# MCU_64.net
KiCad netlist of a schematic drawn in Altium Designer
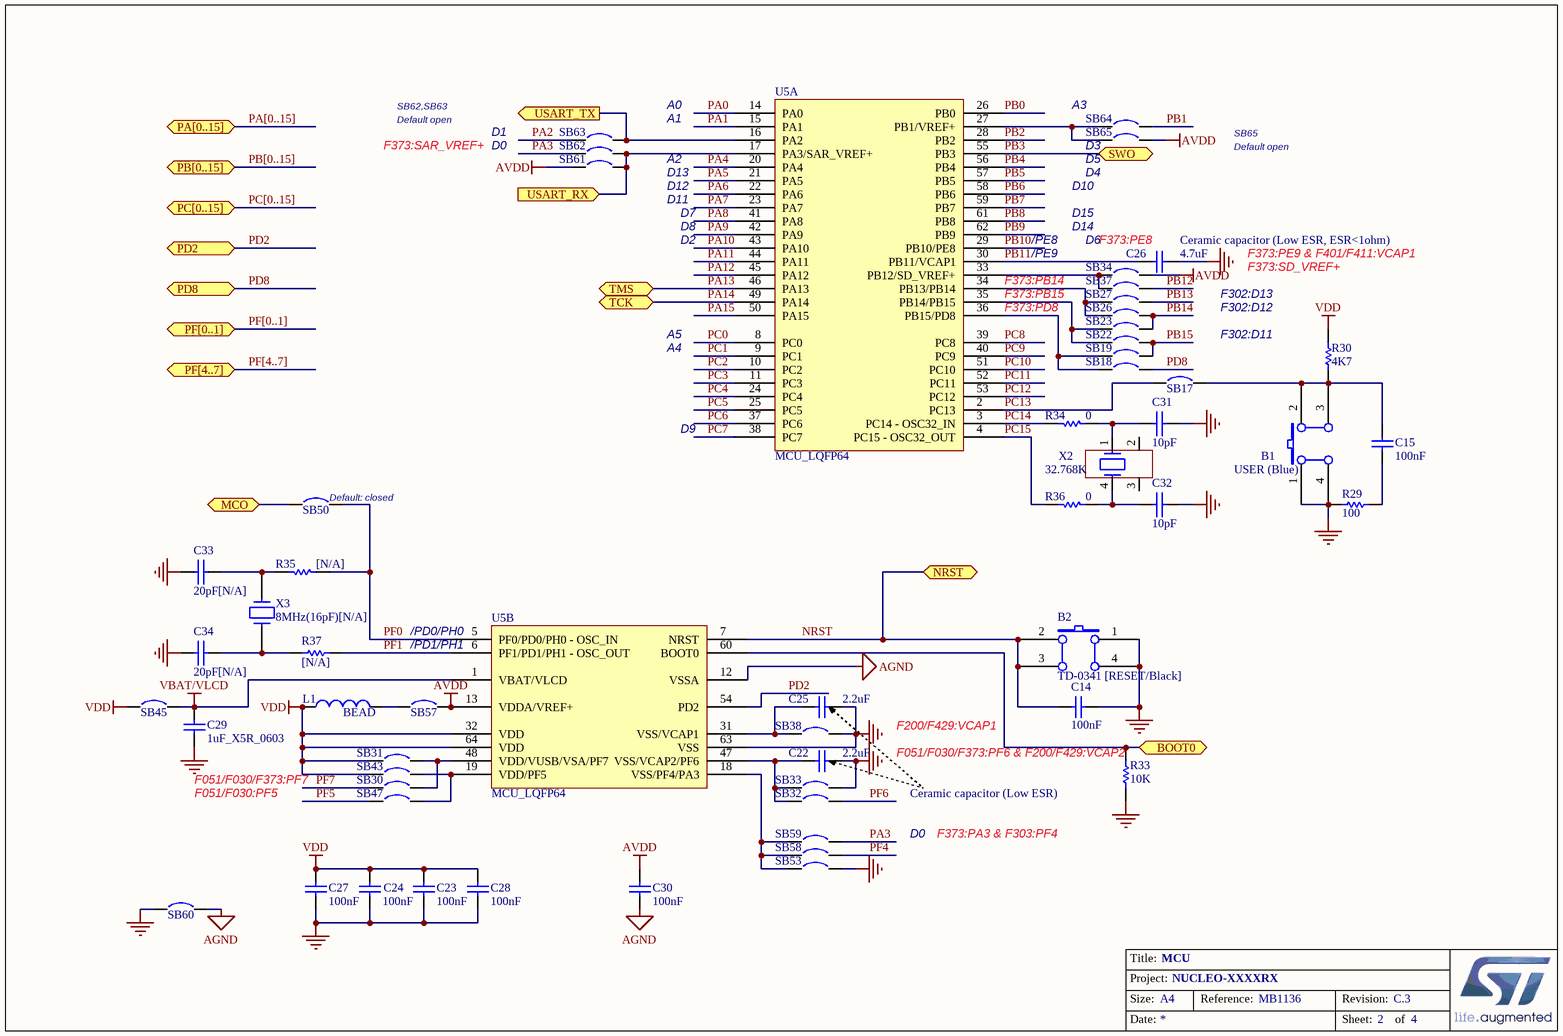
[diagram p0: MCU_64.SchDoc]

(export (version "E")
  (design (tool "Eeschema 10.0.6"))
  (components
    (comp (ref "B1")
      (value "USER (Blue)")
      (footprint "PB10")
      (description "SE PUSHBUTTON")
      (libsource (lib "Documents") (part "SW PUSHBUTTON"))
    )
    (comp (ref "B2")
      (value "TD-0341 [RESET/Black]")
      (footprint "PB10")
      (description "SE PUSHBUTTON")
      (libsource (lib "Documents") (part "SW PUSHBUTTON"))
    )
    (comp (ref "C14")
      (value "100nF")
      (footprint "0603C")
      (description "Capacitor")
      (fields (field (name "PUBLISHER") "Altium Limited"))
      (libsource (lib "Miscellaneous Devices") (part "CAP"))
    )
    (comp (ref "C15")
      (value "100nF")
      (footprint "0603C")
      (description "Capacitor")
      (fields (field (name "PUBLISHER") "Altium Limited"))
      (libsource (lib "Miscellaneous Devices") (part "CAP"))
    )
    (comp (ref "C22")
      (value "2.2uF")
      (footprint "TAN-A")
      (description "Capacitor,2.2uF,16V, X7R,10%,0805,YAGEO")
      (libsource (lib "MCD_TOOLS") (part "Cap_2.2uF_X7R_10%_0805"))
    )
    (comp (ref "C23")
      (value "100nF")
      (footprint "0603C")
      (description "Capacitor")
      (fields (field (name "PUBLISHER") "Altium Limited"))
      (libsource (lib "Miscellaneous Devices") (part "Cap"))
    )
    (comp (ref "C24")
      (value "100nF")
      (footprint "0603C")
      (description "Capacitor")
      (fields (field (name "PUBLISHER") "Altium Limited"))
      (libsource (lib "Miscellaneous Devices") (part "Cap"))
    )
    (comp (ref "C25")
      (value "2.2uF")
      (footprint "TAN-A")
      (description "Capacitor,2.2uF,16V, X7R,10%,0805,YAGEO")
      (libsource (lib "MCD_TOOLS") (part "Cap_2.2uF_X7R_10%_0805"))
    )
    (comp (ref "C26")
      (value "4.7uF")
      (footprint "TAN-A")
      (description "Capacitor,2.2uF,16V, X7R,10%,0805,YAGEO")
      (libsource (lib "MCD_TOOLS") (part "Cap_2.2uF_X7R_10%_0805"))
    )
    (comp (ref "C27")
      (value "100nF")
      (footprint "0603C")
      (description "Capacitor")
      (fields (field (name "PUBLISHER") "Altium Limited"))
      (libsource (lib "Miscellaneous Devices") (part "Cap"))
    )
    (comp (ref "C28")
      (value "100nF")
      (footprint "0603C")
      (description "Capacitor")
      (fields (field (name "PUBLISHER") "Altium Limited"))
      (libsource (lib "Miscellaneous Devices") (part "Cap"))
    )
    (comp (ref "C29")
      (value "1uF_X5R_0603")
      (footprint "0603C")
      (description "0603  X5R 1µF")
      (fields (field (name "TOLERANCE") "10%"))
      (libsource (lib "MB963_1") (part "CAP SMD 0603  X5R 1µF 25V 10%"))
    )
    (comp (ref "C30")
      (value "100nF")
      (footprint "0603C")
      (description "Capacitor")
      (fields (field (name "PUBLISHER") "Altium Limited"))
      (libsource (lib "Miscellaneous Devices") (part "Cap"))
    )
    (comp (ref "C31")
      (value "10pF")
      (footprint "0603C")
      (description "Capacitor")
      (libsource (lib "") (part "CAP_1"))
    )
    (comp (ref "C32")
      (value "10pF")
      (footprint "0603C")
      (description "Capacitor")
      (libsource (lib "") (part "CAP_1"))
    )
    (comp (ref "C33")
      (value "20pF[N/A]")
      (footprint "0603C")
      (description "Capacitor")
      (libsource (lib "*") (part "CAP"))
    )
    (comp (ref "C34")
      (value "20pF[N/A]")
      (footprint "0603C")
      (description "Capacitor")
      (libsource (lib "*") (part "CAP"))
    )
    (comp (ref "L1")
      (value "BEAD")
      (footprint "0603L")
      (description "Inductor")
      (fields (field (name "PUBLISHER") "Altium Limited"))
      (libsource (lib "Miscellaneous Devices") (part "Inductor"))
    )
    (comp (ref "R29")
      (value "100")
      (footprint "0603R")
      (description "Resistor")
      (fields (field (name "PUBLISHER") "Altium Limited"))
      (libsource (lib "") (part "Res1_1"))
    )
    (comp (ref "R30")
      (value "4K7")
      (footprint "0603R")
      (description "Resistor")
      (fields (field (name "PUBLISHER") "Altium Limited"))
      (libsource (lib "Miscellaneous Devices") (part "res1"))
    )
    (comp (ref "R33")
      (value "10K")
      (footprint "0603R")
      (description "Resistor")
      (fields (field (name "PUBLISHER") "Altium Limited"))
      (libsource (lib "Miscellaneous Devices") (part "res1"))
    )
    (comp (ref "R34")
      (value "0")
      (footprint "0603R")
      (description "Resistor")
      (fields (field (name "PUBLISHER") "Altium Limited"))
      (libsource (lib "Miscellaneous Devices") (part "Res1"))
    )
    (comp (ref "R35")
      (value "[N/A]")
      (footprint "0603R")
      (description "Resistor")
      (fields (field (name "PUBLISHER") "Altium Limited"))
      (libsource (lib "Miscellaneous Devices") (part "Res1"))
    )
    (comp (ref "R36")
      (value "0")
      (footprint "0603R")
      (description "Resistor")
      (fields (field (name "PUBLISHER") "Altium Limited"))
      (libsource (lib "Miscellaneous Devices") (part "Res1"))
    )
    (comp (ref "R37")
      (value "[N/A]")
      (footprint "0603R")
      (description "Resistor")
      (fields (field (name "PUBLISHER") "Altium Limited"))
      (libsource (lib "") (part "Res1_1"))
    )
    (comp (ref "SB17")
      (value "Circuit Breaker")
      (footprint "JP2_SMD")
      (fields (field (name "PUBLISHER") "Altium Limited"))
      (libsource (lib "MCD_TOOLS") (part "Circuit Breaker"))
    )
    (comp (ref "SB18")
      (value "Circuit Breaker")
      (footprint "JP2_SMD")
      (fields (field (name "PUBLISHER") "Altium Limited"))
      (libsource (lib "MCD_TOOLS") (part "Circuit Breaker"))
    )
    (comp (ref "SB19")
      (value "Circuit Breaker")
      (footprint "JP2_SMD")
      (fields (field (name "PUBLISHER") "Altium Limited"))
      (libsource (lib "MCD_TOOLS") (part "Circuit Breaker"))
    )
    (comp (ref "SB22")
      (value "Circuit Breaker")
      (footprint "JP2_SMD")
      (fields (field (name "PUBLISHER") "Altium Limited"))
      (libsource (lib "MCD_TOOLS") (part "Circuit Breaker"))
    )
    (comp (ref "SB23")
      (value "Circuit Breaker")
      (footprint "JP2_SMD")
      (fields (field (name "PUBLISHER") "Altium Limited"))
      (libsource (lib "MCD_TOOLS") (part "Circuit Breaker"))
    )
    (comp (ref "SB26")
      (value "Circuit Breaker")
      (footprint "JP2_SMD")
      (fields (field (name "PUBLISHER") "Altium Limited"))
      (libsource (lib "MCD_TOOLS") (part "Circuit Breaker"))
    )
    (comp (ref "SB27")
      (value "Circuit Breaker")
      (footprint "JP2_SMD")
      (fields (field (name "PUBLISHER") "Altium Limited"))
      (libsource (lib "MCD_TOOLS") (part "Circuit Breaker"))
    )
    (comp (ref "SB30")
      (value "Circuit Breaker")
      (footprint "JP2_SMD")
      (fields (field (name "PUBLISHER") "Altium Limited"))
      (libsource (lib "MCD_TOOLS") (part "Circuit Breaker"))
    )
    (comp (ref "SB31")
      (value "Circuit Breaker")
      (footprint "JP2_SMD")
      (fields (field (name "PUBLISHER") "Altium Limited"))
      (libsource (lib "MCD_TOOLS") (part "Circuit Breaker"))
    )
    (comp (ref "SB32")
      (value "Circuit Breaker")
      (footprint "JP2_SMD")
      (fields (field (name "PUBLISHER") "Altium Limited"))
      (libsource (lib "MCD_TOOLS") (part "Circuit Breaker"))
    )
    (comp (ref "SB33")
      (value "Circuit Breaker")
      (footprint "JP2_SMD")
      (fields (field (name "PUBLISHER") "Altium Limited"))
      (libsource (lib "MCD_TOOLS") (part "Circuit Breaker"))
    )
    (comp (ref "SB34")
      (value "Circuit Breaker")
      (footprint "JP2_SMD")
      (fields (field (name "PUBLISHER") "Altium Limited"))
      (libsource (lib "MCD_TOOLS") (part "Circuit Breaker"))
    )
    (comp (ref "SB37")
      (value "Circuit Breaker")
      (footprint "JP2_SMD")
      (fields (field (name "PUBLISHER") "Altium Limited"))
      (libsource (lib "MCD_TOOLS") (part "Circuit Breaker"))
    )
    (comp (ref "SB38")
      (value "Circuit Breaker")
      (footprint "JP2_SMD")
      (fields (field (name "PUBLISHER") "Altium Limited"))
      (libsource (lib "MCD_TOOLS") (part "Circuit Breaker"))
    )
    (comp (ref "SB43")
      (value "Circuit Breaker")
      (footprint "JP2_SMD")
      (fields (field (name "PUBLISHER") "Altium Limited"))
      (libsource (lib "MCD_TOOLS") (part "Circuit Breaker"))
    )
    (comp (ref "SB45")
      (value "Circuit Breaker")
      (footprint "JP2_SMD")
      (fields (field (name "PUBLISHER") "Altium Limited"))
      (libsource (lib "MCD_TOOLS") (part "Circuit Breaker"))
    )
    (comp (ref "SB47")
      (value "Circuit Breaker")
      (footprint "JP2_SMD")
      (fields (field (name "PUBLISHER") "Altium Limited"))
      (libsource (lib "MCD_TOOLS") (part "Circuit Breaker"))
    )
    (comp (ref "SB50")
      (value "Circuit Breaker")
      (footprint "JP2_SMD")
      (fields (field (name "PUBLISHER") "Altium Limited"))
      (libsource (lib "MCD_TOOLS") (part "Circuit Breaker"))
    )
    (comp (ref "SB53")
      (value "Circuit Breaker")
      (footprint "JP2_SMD")
      (fields (field (name "PUBLISHER") "Altium Limited"))
      (libsource (lib "MCD_TOOLS") (part "Circuit Breaker"))
    )
    (comp (ref "SB57")
      (value "Circuit Breaker")
      (footprint "JP2_SMD")
      (fields (field (name "PUBLISHER") "Altium Limited"))
      (libsource (lib "MCD_TOOLS") (part "Circuit Breaker"))
    )
    (comp (ref "SB58")
      (value "Circuit Breaker")
      (footprint "JP2_SMD")
      (fields (field (name "PUBLISHER") "Altium Limited"))
      (libsource (lib "MCD_TOOLS") (part "Circuit Breaker"))
    )
    (comp (ref "SB59")
      (value "Circuit Breaker")
      (footprint "JP2_SMD")
      (fields (field (name "PUBLISHER") "Altium Limited"))
      (libsource (lib "MCD_TOOLS") (part "Circuit Breaker"))
    )
    (comp (ref "SB60")
      (value "Circuit Breaker")
      (footprint "JP2_SMD")
      (fields (field (name "PUBLISHER") "Altium Limited"))
      (libsource (lib "MCD_TOOLS") (part "Circuit Breaker"))
    )
    (comp (ref "SB61")
      (value "Circuit Breaker")
      (footprint "JP2_SMD")
      (fields (field (name "PUBLISHER") "Altium Limited"))
      (libsource (lib "MCD_TOOLS") (part "Circuit Breaker"))
    )
    (comp (ref "SB62")
      (value "Circuit Breaker")
      (footprint "JP2_SMD")
      (fields (field (name "PUBLISHER") "Altium Limited"))
      (libsource (lib "MCD_TOOLS") (part "Circuit Breaker"))
    )
    (comp (ref "SB63")
      (value "Circuit Breaker")
      (footprint "JP2_SMD")
      (fields (field (name "PUBLISHER") "Altium Limited"))
      (libsource (lib "MCD_TOOLS") (part "Circuit Breaker"))
    )
    (comp (ref "SB64")
      (value "Circuit Breaker")
      (footprint "JP2_SMD")
      (fields (field (name "PUBLISHER") "Altium Limited"))
      (libsource (lib "MCD_TOOLS") (part "Circuit Breaker"))
    )
    (comp (ref "SB65")
      (value "Circuit Breaker")
      (footprint "JP2_SMD")
      (fields (field (name "PUBLISHER") "Altium Limited"))
      (libsource (lib "MCD_TOOLS") (part "Circuit Breaker"))
    )
    (comp (ref "U5")
      (value "MCU_LQFP64")
      (footprint "LQFP64")
      (libsource (lib "Nucleo_64") (part "MCU_LQFP64"))
    )
    (comp (ref "X2") (value "32.768K") (footprint "XTAL_4SM_8X3R8") (libsource (lib "*") (part "MC306")))
    (comp (ref "X3")
      (value "8MHz(16pF)[N/A]")
      (footprint "XTAL1")
      (description "Crystal")
      (libsource (lib "*") (part "CRYSTAL"))
    )
  )
  (nets
    (net (code "1") (name "/BOOT0") (class "Default")
      (node (ref "R33") (pin "1") (pinfunction "1_1") (pintype "passive"))
      (node (ref "U5") (pin "60") (pinfunction "BOOT0_60") (pintype "passive"))
    )
    (net (code "2") (name "/MCO") (class "Default")
      (node (ref "SB50") (pin "1") (pinfunction "1_1") (pintype "passive"))
    )
    (net (code "3") (name "/NRST") (class "Default")
      (node (ref "B2") (pin "2") (pinfunction "B0_2") (pintype "passive"))
      (node (ref "B2") (pin "3") (pinfunction "B1_3") (pintype "passive"))
      (node (ref "C14") (pin "2") (pinfunction "2_2") (pintype "passive"))
      (node (ref "U5") (pin "7") (pinfunction "NRST_7") (pintype "passive"))
    )
    (net (code "4") (name "/PA0") (class "Default")
      (node (ref "U5") (pin "14") (pinfunction "PA0_14") (pintype "passive"))
    )
    (net (code "5") (name "/PA1") (class "Default")
      (node (ref "U5") (pin "15") (pinfunction "PA1_15") (pintype "passive"))
    )
    (net (code "6") (name "/PA2") (class "Default")
      (node (ref "SB63") (pin "1") (pinfunction "1_1") (pintype "passive"))
    )
    (net (code "7") (name "/PA3") (class "Default")
      (node (ref "SB59") (pin "2") (pinfunction "2_2") (pintype "passive"))
      (node (ref "SB62") (pin "1") (pinfunction "1_1") (pintype "passive"))
    )
    (net (code "8") (name "/PA4") (class "Default")
      (node (ref "U5") (pin "20") (pinfunction "PA4_20") (pintype "passive"))
    )
    (net (code "9") (name "/PA5") (class "Default")
      (node (ref "U5") (pin "21") (pinfunction "PA5_21") (pintype "passive"))
    )
    (net (code "10") (name "/PA6") (class "Default")
      (node (ref "U5") (pin "22") (pinfunction "PA6_22") (pintype "passive"))
    )
    (net (code "11") (name "/PA7") (class "Default")
      (node (ref "U5") (pin "23") (pinfunction "PA7_23") (pintype "passive"))
    )
    (net (code "12") (name "/PA8") (class "Default")
      (node (ref "U5") (pin "41") (pinfunction "PA8_41") (pintype "passive"))
    )
    (net (code "13") (name "/PA9") (class "Default")
      (node (ref "U5") (pin "42") (pinfunction "PA9_42") (pintype "passive"))
    )
    (net (code "14") (name "/PA10") (class "Default")
      (node (ref "U5") (pin "43") (pinfunction "PA10_43") (pintype "passive"))
    )
    (net (code "15") (name "/PA11") (class "Default")
      (node (ref "U5") (pin "44") (pinfunction "PA11_44") (pintype "passive"))
    )
    (net (code "16") (name "/PA12") (class "Default")
      (node (ref "U5") (pin "45") (pinfunction "PA12_45") (pintype "passive"))
    )
    (net (code "17") (name "/PA13") (class "Default")
      (node (ref "U5") (pin "46") (pinfunction "PA13_46") (pintype "passive"))
    )
    (net (code "18") (name "/PA14") (class "Default")
      (node (ref "U5") (pin "49") (pinfunction "PA14_49") (pintype "passive"))
    )
    (net (code "19") (name "/PA15") (class "Default")
      (node (ref "U5") (pin "50") (pinfunction "PA15_50") (pintype "passive"))
    )
    (net (code "21") (name "/PB0") (class "Default")
      (node (ref "U5") (pin "26") (pinfunction "PB0_26") (pintype "passive"))
    )
    (net (code "22") (name "/PB1") (class "Default")
      (node (ref "SB64") (pin "2") (pinfunction "2_2") (pintype "passive"))
    )
    (net (code "23") (name "/PB2") (class "Default")
      (node (ref "U5") (pin "28") (pinfunction "PB2_28") (pintype "passive"))
    )
    (net (code "24") (name "/PB3") (class "Default")
      (node (ref "U5") (pin "55") (pinfunction "PB3_55") (pintype "passive"))
    )
    (net (code "25") (name "/PB4") (class "Default")
      (node (ref "U5") (pin "56") (pinfunction "PB4_56") (pintype "passive"))
    )
    (net (code "26") (name "/PB5") (class "Default")
      (node (ref "U5") (pin "57") (pinfunction "PB5_57") (pintype "passive"))
    )
    (net (code "27") (name "/PB6") (class "Default")
      (node (ref "U5") (pin "58") (pinfunction "PB6_58") (pintype "passive"))
    )
    (net (code "28") (name "/PB7") (class "Default")
      (node (ref "U5") (pin "59") (pinfunction "PB7_59") (pintype "passive"))
    )
    (net (code "29") (name "/PB8") (class "Default")
      (node (ref "U5") (pin "61") (pinfunction "PB8_61") (pintype "passive"))
    )
    (net (code "30") (name "/PB9") (class "Default")
      (node (ref "U5") (pin "62") (pinfunction "PB9_62") (pintype "passive"))
    )
    (net (code "31") (name "/PB10") (class "Default")
      (node (ref "U5") (pin "29") (pinfunction "PB10/PE8_29") (pintype "passive"))
    )
    (net (code "32") (name "/PB11") (class "Default")
      (node (ref "C26") (pin "1") (pinfunction "1_1") (pintype "passive"))
      (node (ref "U5") (pin "30") (pinfunction "PB11/VCAP1_30") (pintype "passive"))
    )
    (net (code "33") (name "/PB12") (class "Default")
      (node (ref "SB37") (pin "2") (pinfunction "2_2") (pintype "passive"))
    )
    (net (code "34") (name "/PB13") (class "Default")
      (node (ref "SB27") (pin "2") (pinfunction "2_2") (pintype "passive"))
    )
    (net (code "35") (name "/PB14") (class "Default")
      (node (ref "SB23") (pin "2") (pinfunction "2_2") (pintype "passive"))
      (node (ref "SB26") (pin "2") (pinfunction "2_2") (pintype "passive"))
    )
    (net (code "36") (name "/PB15") (class "Default")
      (node (ref "SB19") (pin "2") (pinfunction "2_2") (pintype "passive"))
      (node (ref "SB22") (pin "2") (pinfunction "2_2") (pintype "passive"))
    )
    (net (code "38") (name "/PC0") (class "Default")
      (node (ref "U5") (pin "8") (pinfunction "PC0_8") (pintype "passive"))
    )
    (net (code "39") (name "/PC1") (class "Default")
      (node (ref "U5") (pin "9") (pinfunction "PC1_9") (pintype "passive"))
    )
    (net (code "40") (name "/PC2") (class "Default")
      (node (ref "U5") (pin "10") (pinfunction "PC2_10") (pintype "passive"))
    )
    (net (code "41") (name "/PC3") (class "Default")
      (node (ref "U5") (pin "11") (pinfunction "PC3_11") (pintype "passive"))
    )
    (net (code "42") (name "/PC4") (class "Default")
      (node (ref "U5") (pin "24") (pinfunction "PC4_24") (pintype "passive"))
    )
    (net (code "43") (name "/PC5") (class "Default")
      (node (ref "U5") (pin "25") (pinfunction "PC5_25") (pintype "passive"))
    )
    (net (code "44") (name "/PC6") (class "Default")
      (node (ref "U5") (pin "37") (pinfunction "PC6_37") (pintype "passive"))
    )
    (net (code "45") (name "/PC7") (class "Default")
      (node (ref "U5") (pin "38") (pinfunction "PC7_38") (pintype "passive"))
    )
    (net (code "46") (name "/PC8") (class "Default")
      (node (ref "U5") (pin "39") (pinfunction "PC8_39") (pintype "passive"))
    )
    (net (code "47") (name "/PC9") (class "Default")
      (node (ref "U5") (pin "40") (pinfunction "PC9_40") (pintype "passive"))
    )
    (net (code "48") (name "/PC10") (class "Default")
      (node (ref "U5") (pin "51") (pinfunction "PC10_51") (pintype "passive"))
    )
    (net (code "49") (name "/PC11") (class "Default")
      (node (ref "U5") (pin "52") (pinfunction "PC11_52") (pintype "passive"))
    )
    (net (code "50") (name "/PC12") (class "Default")
      (node (ref "U5") (pin "53") (pinfunction "PC12_53") (pintype "passive"))
    )
    (net (code "51") (name "/PC13") (class "Default")
      (node (ref "SB17") (pin "1") (pinfunction "1_1") (pintype "passive"))
      (node (ref "U5") (pin "2") (pinfunction "PC13_2") (pintype "passive"))
    )
    (net (code "52") (name "/PC14") (class "Default")
      (node (ref "R34") (pin "2") (pinfunction "2_2") (pintype "passive"))
      (node (ref "U5") (pin "3") (pinfunction "PC14_-_OSC32_IN_3") (pintype "passive"))
    )
    (net (code "53") (name "/PC15") (class "Default")
      (node (ref "R36") (pin "2") (pinfunction "2_2") (pintype "passive"))
      (node (ref "U5") (pin "4") (pinfunction "PC15_-_OSC32_OUT_4") (pintype "passive"))
    )
    (net (code "55") (name "/PD2") (class "Default")
      (node (ref "U5") (pin "54") (pinfunction "PD2_54") (pintype "passive"))
    )
    (net (code "56") (name "/PD8") (class "Default")
      (node (ref "SB18") (pin "2") (pinfunction "2_2") (pintype "passive"))
    )
    (net (code "57") (name "/PF0") (class "Default")
      (node (ref "R35") (pin "1") (pinfunction "1_1") (pintype "passive"))
      (node (ref "SB50") (pin "2") (pinfunction "2_2") (pintype "passive"))
      (node (ref "U5") (pin "5") (pinfunction "PF0/PD0/PH0_-_OSC_IN_5") (pintype "passive"))
    )
    (net (code "58") (name "/PF1") (class "Default")
      (node (ref "R37") (pin "1") (pinfunction "1_1") (pintype "passive"))
      (node (ref "U5") (pin "6") (pinfunction "PF1/PD1/PH1_-_OSC_OUT_6") (pintype "passive"))
    )
    (net (code "59") (name "/PF4") (class "Default")
      (node (ref "SB58") (pin "2") (pinfunction "2_2") (pintype "passive"))
    )
    (net (code "60") (name "/PF5") (class "Default")
      (node (ref "SB47") (pin "1") (pinfunction "1_1") (pintype "passive"))
    )
    (net (code "61") (name "/PF6") (class "Default")
      (node (ref "SB32") (pin "2") (pinfunction "2_2") (pintype "passive"))
    )
    (net (code "62") (name "/PF7") (class "Default")
      (node (ref "SB30") (pin "1") (pinfunction "1_1") (pintype "passive"))
    )
    (net (code "65") (name "/USART_RX") (class "Default")
      (node (ref "SB61") (pin "2") (pinfunction "2_2") (pintype "passive"))
      (node (ref "SB62") (pin "2") (pinfunction "2_2") (pintype "passive"))
      (node (ref "U5") (pin "17") (pinfunction "PA3/SAR_VREF+_17") (pintype "passive"))
    )
    (net (code "66") (name "/USART_TX") (class "Default")
      (node (ref "SB63") (pin "2") (pinfunction "2_2") (pintype "passive"))
      (node (ref "U5") (pin "16") (pinfunction "PA2_16") (pintype "passive"))
    )
    (net (code "67") (name "AGND") (class "Default")
      (node (ref "C30") (pin "2") (pinfunction "2_2") (pintype "passive"))
      (node (ref "SB60") (pin "2") (pinfunction "2_2") (pintype "passive"))
      (node (ref "U5") (pin "12") (pinfunction "VSSA_12") (pintype "passive"))
    )
    (net (code "68") (name "AVDD") (class "Default")
      (node (ref "C30") (pin "1") (pinfunction "1_1") (pintype "passive"))
      (node (ref "SB34") (pin "2") (pinfunction "2_2") (pintype "passive"))
      (node (ref "SB57") (pin "2") (pinfunction "2_2") (pintype "passive"))
      (node (ref "SB61") (pin "1") (pinfunction "1_1") (pintype "passive"))
      (node (ref "SB65") (pin "2") (pinfunction "2_2") (pintype "passive"))
      (node (ref "U5") (pin "13") (pinfunction "VDDA/VREF+_13") (pintype "passive"))
    )
    (net (code "69") (name "GND") (class "Default")
      (node (ref "B1") (pin "1") (pinfunction "A0_1") (pintype "passive"))
      (node (ref "B1") (pin "4") (pinfunction "A1_4") (pintype "passive"))
      (node (ref "B2") (pin "1") (pinfunction "A0_1") (pintype "passive"))
      (node (ref "B2") (pin "4") (pinfunction "A1_4") (pintype "passive"))
      (node (ref "C14") (pin "1") (pinfunction "1_1") (pintype "passive"))
      (node (ref "C22") (pin "2") (pinfunction "2_2") (pintype "passive"))
      (node (ref "C23") (pin "2") (pinfunction "2_2") (pintype "passive"))
      (node (ref "C24") (pin "2") (pinfunction "2_2") (pintype "passive"))
      (node (ref "C25") (pin "2") (pinfunction "2_2") (pintype "passive"))
      (node (ref "C26") (pin "2") (pinfunction "2_2") (pintype "passive"))
      (node (ref "C27") (pin "2") (pinfunction "2_2") (pintype "passive"))
      (node (ref "C28") (pin "2") (pinfunction "2_2") (pintype "passive"))
      (node (ref "C29") (pin "2") (pinfunction "2_2") (pintype "passive"))
      (node (ref "C31") (pin "2") (pinfunction "2_2") (pintype "passive"))
      (node (ref "C32") (pin "2") (pinfunction "2_2") (pintype "passive"))
      (node (ref "C33") (pin "2") (pinfunction "2_2") (pintype "passive"))
      (node (ref "C34") (pin "2") (pinfunction "2_2") (pintype "passive"))
      (node (ref "R29") (pin "1") (pinfunction "1_1") (pintype "passive"))
      (node (ref "R33") (pin "2") (pinfunction "2_2") (pintype "passive"))
      (node (ref "SB33") (pin "2") (pinfunction "2_2") (pintype "passive"))
      (node (ref "SB38") (pin "2") (pinfunction "2_2") (pintype "passive"))
      (node (ref "SB53") (pin "2") (pinfunction "2_2") (pintype "passive"))
      (node (ref "SB60") (pin "1") (pinfunction "1_1") (pintype "passive"))
      (node (ref "U5") (pin "63") (pinfunction "VSS_63") (pintype "passive"))
    )
    (net (code "70") (name "Net-(B1-B0)") (class "Default")
      (node (ref "B1") (pin "2") (pinfunction "B0_2") (pintype "passive"))
      (node (ref "B1") (pin "3") (pinfunction "B1_3") (pintype "passive"))
      (node (ref "C15") (pin "2") (pinfunction "2_2") (pintype "passive"))
      (node (ref "R30") (pin "1") (pinfunction "1_1") (pintype "passive"))
      (node (ref "SB17") (pin "2") (pinfunction "2_2") (pintype "passive"))
    )
    (net (code "71") (name "Net-(C15-Pad1)") (class "Default")
      (node (ref "C15") (pin "1") (pinfunction "1_1") (pintype "passive"))
      (node (ref "R29") (pin "2") (pinfunction "2_2") (pintype "passive"))
    )
    (net (code "72") (name "Net-(C31-Pad1)") (class "Default")
      (node (ref "C31") (pin "1") (pinfunction "1_1") (pintype "passive"))
      (node (ref "R34") (pin "1") (pinfunction "1_1") (pintype "passive"))
      (node (ref "X2") (pin "1") (pinfunction "1_1") (pintype "passive"))
    )
    (net (code "73") (name "Net-(C32-Pad1)") (class "Default")
      (node (ref "C32") (pin "1") (pinfunction "1_1") (pintype "passive"))
      (node (ref "R36") (pin "1") (pinfunction "1_1") (pintype "passive"))
      (node (ref "X2") (pin "4") (pinfunction "4_4") (pintype "passive"))
    )
    (net (code "74") (name "Net-(C33-Pad1)") (class "Default")
      (node (ref "C33") (pin "1") (pinfunction "1_1") (pintype "passive"))
      (node (ref "R35") (pin "2") (pinfunction "2_2") (pintype "passive"))
      (node (ref "X3") (pin "2") (pinfunction "2_2") (pintype "passive"))
    )
    (net (code "75") (name "Net-(C34-Pad1)") (class "Default")
      (node (ref "C34") (pin "1") (pinfunction "1_1") (pintype "passive"))
      (node (ref "R37") (pin "2") (pinfunction "2_2") (pintype "passive"))
      (node (ref "X3") (pin "1") (pinfunction "1_1") (pintype "passive"))
    )
    (net (code "76") (name "Net-(L1-Pad2)") (class "Default")
      (node (ref "L1") (pin "2") (pinfunction "2_2") (pintype "passive"))
      (node (ref "SB57") (pin "1") (pinfunction "1_1") (pintype "passive"))
    )
    (net (code "77") (name "Net-(U5A-PB1{slash}VREF+)") (class "Default")
      (node (ref "SB64") (pin "1") (pinfunction "1_1") (pintype "passive"))
      (node (ref "SB65") (pin "1") (pinfunction "1_1") (pintype "passive"))
      (node (ref "U5") (pin "27") (pinfunction "PB1/VREF+_27") (pintype "passive"))
    )
    (net (code "78") (name "Net-(U5A-PB12{slash}SD_VREF+)") (class "Default")
      (node (ref "SB34") (pin "1") (pinfunction "1_1") (pintype "passive"))
      (node (ref "SB37") (pin "1") (pinfunction "1_1") (pintype "passive"))
      (node (ref "U5") (pin "33") (pinfunction "PB12/SD_VREF+_33") (pintype "passive"))
    )
    (net (code "79") (name "Net-(U5A-PB13{slash}PB14)") (class "Default")
      (node (ref "SB26") (pin "1") (pinfunction "1_1") (pintype "passive"))
      (node (ref "SB27") (pin "1") (pinfunction "1_1") (pintype "passive"))
      (node (ref "U5") (pin "34") (pinfunction "PB13/PB14_34") (pintype "passive"))
    )
    (net (code "80") (name "Net-(U5A-PB14{slash}PB15)") (class "Default")
      (node (ref "SB22") (pin "1") (pinfunction "1_1") (pintype "passive"))
      (node (ref "SB23") (pin "1") (pinfunction "1_1") (pintype "passive"))
      (node (ref "U5") (pin "35") (pinfunction "PB14/PB15_35") (pintype "passive"))
    )
    (net (code "81") (name "Net-(U5A-PB15{slash}PD8)") (class "Default")
      (node (ref "SB18") (pin "1") (pinfunction "1_1") (pintype "passive"))
      (node (ref "SB19") (pin "1") (pinfunction "1_1") (pintype "passive"))
      (node (ref "U5") (pin "36") (pinfunction "PB15/PD8_36") (pintype "passive"))
    )
    (net (code "82") (name "Net-(U5B-VDD{slash}PF5)") (class "Default")
      (node (ref "SB43") (pin "2") (pinfunction "2_2") (pintype "passive"))
      (node (ref "SB47") (pin "2") (pinfunction "2_2") (pintype "passive"))
      (node (ref "U5") (pin "19") (pinfunction "VDD/PF5_19") (pintype "passive"))
    )
    (net (code "83") (name "Net-(U5B-VDD{slash}VUSB{slash}VSA{slash}PF7)") (class "Default")
      (node (ref "SB30") (pin "2") (pinfunction "2_2") (pintype "passive"))
      (node (ref "SB31") (pin "2") (pinfunction "2_2") (pintype "passive"))
      (node (ref "U5") (pin "48") (pinfunction "VDD/VUSB/VSA/PF7_48") (pintype "passive"))
    )
    (net (code "84") (name "Net-(U5B-VSS{slash}PF4{slash}PA3)") (class "Default")
      (node (ref "SB53") (pin "1") (pinfunction "1_1") (pintype "passive"))
      (node (ref "SB58") (pin "1") (pinfunction "1_1") (pintype "passive"))
      (node (ref "SB59") (pin "1") (pinfunction "1_1") (pintype "passive"))
      (node (ref "U5") (pin "18") (pinfunction "VSS/PF4/PA3_18") (pintype "passive"))
    )
    (net (code "85") (name "Net-(U5B-VSS{slash}VCAP1)") (class "Default")
      (node (ref "C25") (pin "1") (pinfunction "1_1") (pintype "passive"))
      (node (ref "SB38") (pin "1") (pinfunction "1_1") (pintype "passive"))
      (node (ref "U5") (pin "31") (pinfunction "VSS/VCAP1_31") (pintype "passive"))
    )
    (net (code "86") (name "Net-(U5B-VSS{slash}VCAP2{slash}PF6)") (class "Default")
      (node (ref "C22") (pin "1") (pinfunction "1_1") (pintype "passive"))
      (node (ref "SB32") (pin "1") (pinfunction "1_1") (pintype "passive"))
      (node (ref "SB33") (pin "1") (pinfunction "1_1") (pintype "passive"))
      (node (ref "U5") (pin "47") (pinfunction "VSS/VCAP2/PF6_47") (pintype "passive"))
    )
    (net (code "87") (name "VBAT{slash}VLCD") (class "Default")
      (node (ref "C29") (pin "1") (pinfunction "1_1") (pintype "passive"))
      (node (ref "SB45") (pin "2") (pinfunction "2_2") (pintype "passive"))
      (node (ref "U5") (pin "1") (pinfunction "VBAT/VLCD_1") (pintype "passive"))
    )
    (net (code "88") (name "VDD") (class "Default")
      (node (ref "C23") (pin "1") (pinfunction "1_1") (pintype "passive"))
      (node (ref "C24") (pin "1") (pinfunction "1_1") (pintype "passive"))
      (node (ref "C27") (pin "1") (pinfunction "1_1") (pintype "passive"))
      (node (ref "C28") (pin "1") (pinfunction "1_1") (pintype "passive"))
      (node (ref "L1") (pin "1") (pinfunction "1_1") (pintype "passive"))
      (node (ref "R30") (pin "2") (pinfunction "2_2") (pintype "passive"))
      (node (ref "SB31") (pin "1") (pinfunction "1_1") (pintype "passive"))
      (node (ref "SB43") (pin "1") (pinfunction "1_1") (pintype "passive"))
      (node (ref "SB45") (pin "1") (pinfunction "1_1") (pintype "passive"))
      (node (ref "U5") (pin "32") (pinfunction "VDD_32") (pintype "passive"))
      (node (ref "U5") (pin "64") (pinfunction "VDD_64") (pintype "passive"))
    )
    (net (code "89") (name "unconnected-(X2-Pad2)") (class "Default")
      (node (ref "X2") (pin "2") (pinfunction "2_2") (pintype "passive"))
    )
    (net (code "90") (name "unconnected-(X2-Pad3)") (class "Default")
      (node (ref "X2") (pin "3") (pinfunction "3_3") (pintype "passive"))
    )
  )
)
